# BusDistribution.net
KiCad netlist of a schematic drawn in Altium Designer
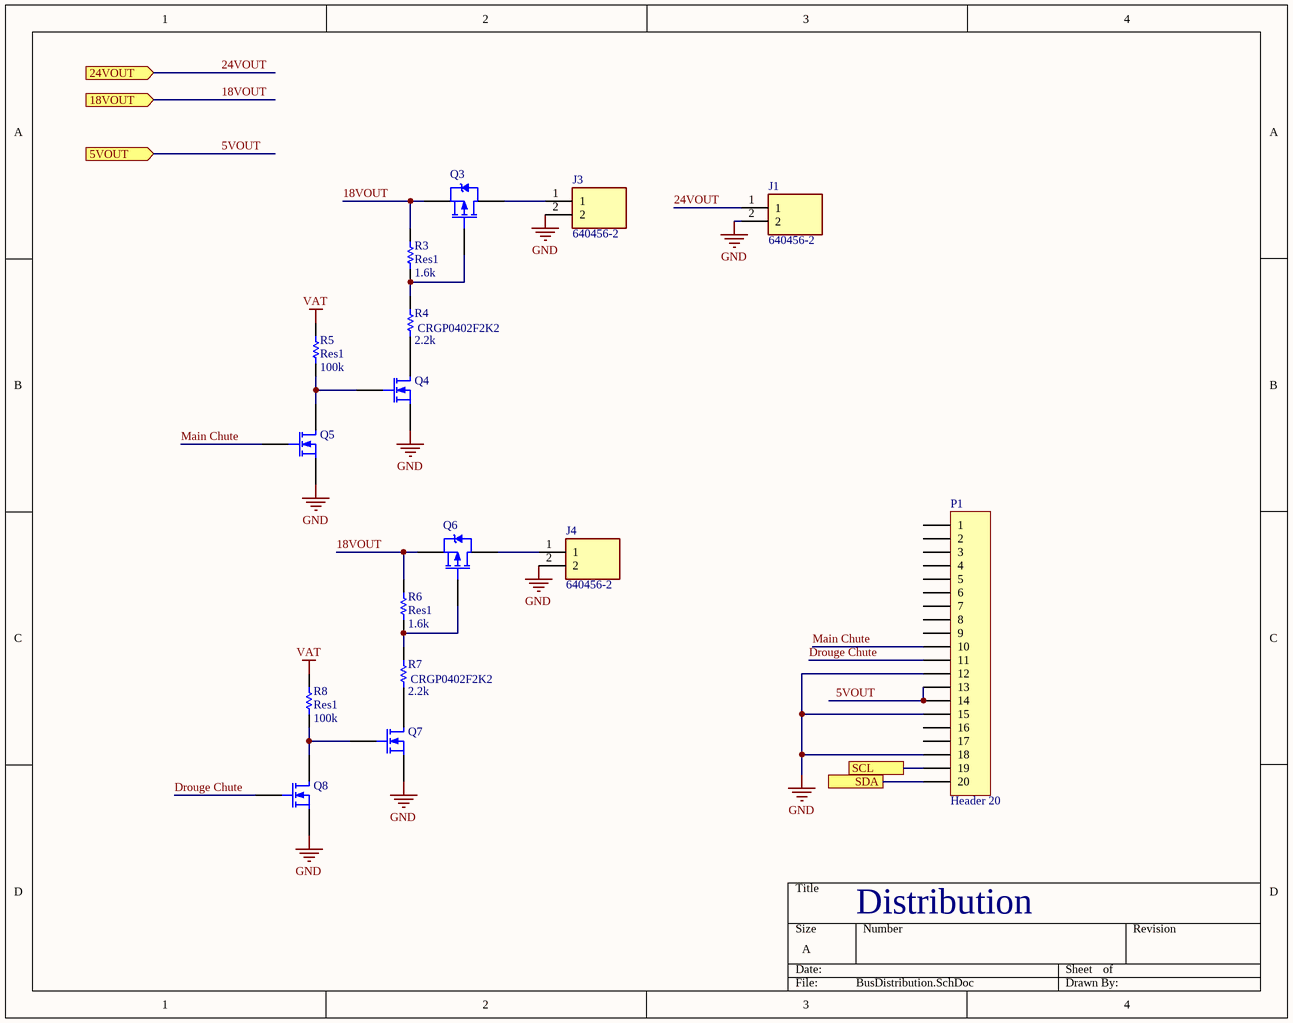
[diagram p0: BusDistribution.SchDoc]

(export (version "E")
  (design (tool "Eeschema 10.0.6"))
  (components
    (comp (ref "J1")
      (value "640456-2")
      (footprint "16404562")
      (description "Connector")
      (fields (field (name "MOUSER PART NUMBER") "571-6404562") (field (name "RS PART NUMBER") "1320355P"))
      (libsource (lib "*") (part "640456-2"))
    )
    (comp (ref "J3")
      (value "640456-2")
      (footprint "16404562")
      (description "Connector")
      (fields (field (name "MOUSER PART NUMBER") "571-6404562") (field (name "RS PART NUMBER") "1320355P"))
      (libsource (lib "*") (part "640456-2"))
    )
    (comp (ref "J4")
      (value "640456-2")
      (footprint "16404562")
      (description "Connector")
      (fields (field (name "MOUSER PART NUMBER") "571-6404562") (field (name "RS PART NUMBER") "1320355P"))
      (libsource (lib "*") (part "640456-2"))
    )
    (comp (ref "P1")
      (value "Header 20")
      (footprint "HDR1X20")
      (description "Header, 20-Pin")
      (fields (field (name "PUBLISHER") "Altium Limited"))
      (libsource (lib "Miscellaneous Connectors") (part "Header 20"))
    )
    (comp (ref "Q3")
      (value "MED power PMOS")
      (footprint "SOT23_L")
      (description "P-Channel Power MOSFET")
      (fields (field (name "PUBLISHER") "Altium Limited"))
      (libsource (lib "Miscellaneous Devices") (part "PMOS-2"))
    )
    (comp (ref "Q4")
      (value "Low Power NMOS")
      (footprint "SOT23_L")
      (description "N-Channel MOSFET")
      (fields (field (name "PUBLISHER") "Altium Limited"))
      (libsource (lib "Miscellaneous Devices") (part "MOSFET-N"))
    )
    (comp (ref "Q5")
      (value "Low power NMOS")
      (footprint "SOT23_L")
      (description "N-Channel MOSFET")
      (fields (field (name "PUBLISHER") "Altium Limited"))
      (libsource (lib "Miscellaneous Devices") (part "MOSFET-N"))
    )
    (comp (ref "Q6")
      (value "MED power PMOS")
      (footprint "SOT23_L")
      (description "P-Channel Power MOSFET")
      (fields (field (name "PUBLISHER") "Altium Limited"))
      (libsource (lib "Miscellaneous Devices") (part "PMOS-2"))
    )
    (comp (ref "Q7")
      (value "Low Power NMOS")
      (footprint "SOT23_L")
      (description "N-Channel MOSFET")
      (fields (field (name "PUBLISHER") "Altium Limited"))
      (libsource (lib "Miscellaneous Devices") (part "MOSFET-N"))
    )
    (comp (ref "Q8")
      (value "Low Power NMOS")
      (footprint "SOT23_L")
      (description "N-Channel MOSFET")
      (fields (field (name "PUBLISHER") "Altium Limited"))
      (libsource (lib "Miscellaneous Devices") (part "MOSFET-N"))
    )
    (comp (ref "R3")
      (value "Res1")
      (footprint "0402")
      (description "Resistor")
      (fields (field (name "ALTIUM_VALUE") "1.6k") (field (name "PUBLISHER") "Altium Limited"))
      (libsource (lib "Miscellaneous Devices") (part "Res1"))
    )
    (comp (ref "R4")
      (value "CRGP0402F2K2")
      (footprint "0402")
      (description "2.2 kOhms ±1% 0.125W, 1/8W Chip Resistor 0402 (1005 Metric) Pulse Withstanding Thick Film")
      (fields (field (name "ALTIUM_VALUE") "2.2k") (field (name "MFG") "TE Connectivity Passive Product"))
      (libsource (lib "Miscellaneous Devices") (part "Res1"))
    )
    (comp (ref "R5")
      (value "Res1")
      (footprint "0402")
      (description "Resistor")
      (fields (field (name "ALTIUM_VALUE") "100k") (field (name "PUBLISHER") "Altium Limited"))
      (libsource (lib "Miscellaneous Devices") (part "Res1"))
    )
    (comp (ref "R6")
      (value "Res1")
      (footprint "0402")
      (description "Resistor")
      (fields (field (name "ALTIUM_VALUE") "1.6k") (field (name "PUBLISHER") "Altium Limited"))
      (libsource (lib "Miscellaneous Devices") (part "Res1"))
    )
    (comp (ref "R7")
      (value "CRGP0402F2K2")
      (footprint "0402")
      (description "2.2 kOhms ±1% 0.125W, 1/8W Chip Resistor 0402 (1005 Metric) Pulse Withstanding Thick Film")
      (fields (field (name "ALTIUM_VALUE") "2.2k") (field (name "MFG") "TE Connectivity Passive Product"))
      (libsource (lib "Miscellaneous Devices") (part "Res1"))
    )
    (comp (ref "R8")
      (value "Res1")
      (footprint "0402")
      (description "Resistor")
      (fields (field (name "ALTIUM_VALUE") "100k") (field (name "PUBLISHER") "Altium Limited"))
      (libsource (lib "Miscellaneous Devices") (part "Res1"))
    )
  )
  (nets
    (net (code "1") (name "/5VOUT") (class "Default")
      (node (ref "P1") (pin "13") (pinfunction "13_13") (pintype "passive"))
      (node (ref "P1") (pin "14") (pinfunction "14_14") (pintype "passive"))
    )
    (net (code "2") (name "/18VOUT") (class "Default")
      (node (ref "Q3") (pin "3") (pinfunction "S_3") (pintype "passive"))
      (node (ref "Q6") (pin "3") (pinfunction "S_3") (pintype "passive"))
      (node (ref "R3") (pin "2") (pinfunction "2_2") (pintype "passive"))
      (node (ref "R6") (pin "2") (pinfunction "2_2") (pintype "passive"))
    )
    (net (code "3") (name "/24VOUT") (class "Default")
      (node (ref "J1") (pin "1") (pinfunction "1_1") (pintype "passive"))
    )
    (net (code "4") (name "/Drouge Chute") (class "Default")
      (node (ref "P1") (pin "11") (pinfunction "11_11") (pintype "passive"))
      (node (ref "Q8") (pin "2") (pinfunction "G_2") (pintype "passive"))
    )
    (net (code "5") (name "/Main Chute") (class "Default")
      (node (ref "P1") (pin "10") (pinfunction "10_10") (pintype "passive"))
      (node (ref "Q5") (pin "2") (pinfunction "G_2") (pintype "passive"))
    )
    (net (code "6") (name "/SCL") (class "Default")
      (node (ref "P1") (pin "19") (pinfunction "19_19") (pintype "passive"))
    )
    (net (code "7") (name "/SDA") (class "Default")
      (node (ref "P1") (pin "20") (pinfunction "20_20") (pintype "passive"))
    )
    (net (code "8") (name "GND") (class "Default")
      (node (ref "J1") (pin "2") (pinfunction "2_2") (pintype "passive"))
      (node (ref "J3") (pin "2") (pinfunction "2_2") (pintype "passive"))
      (node (ref "J4") (pin "2") (pinfunction "2_2") (pintype "passive"))
      (node (ref "P1") (pin "12") (pinfunction "12_12") (pintype "passive"))
      (node (ref "P1") (pin "15") (pinfunction "15_15") (pintype "passive"))
      (node (ref "P1") (pin "18") (pinfunction "18_18") (pintype "passive"))
      (node (ref "Q4") (pin "3") (pinfunction "S_3") (pintype "passive"))
      (node (ref "Q5") (pin "3") (pinfunction "S_3") (pintype "passive"))
      (node (ref "Q7") (pin "3") (pinfunction "S_3") (pintype "passive"))
      (node (ref "Q8") (pin "3") (pinfunction "S_3") (pintype "passive"))
    )
    (net (code "9") (name "Net-(Q3-D)") (class "Default")
      (node (ref "J3") (pin "1") (pinfunction "1_1") (pintype "passive"))
      (node (ref "Q3") (pin "2") (pinfunction "D_2") (pintype "passive"))
    )
    (net (code "10") (name "Net-(Q3-G)") (class "Default")
      (node (ref "Q3") (pin "1") (pinfunction "G_1") (pintype "passive"))
      (node (ref "R3") (pin "1") (pinfunction "1_1") (pintype "passive"))
      (node (ref "R4") (pin "2") (pinfunction "2_2") (pintype "passive"))
    )
    (net (code "11") (name "Net-(Q4-D)") (class "Default")
      (node (ref "Q4") (pin "1") (pinfunction "D_1") (pintype "passive"))
      (node (ref "R4") (pin "1") (pinfunction "1_1") (pintype "passive"))
    )
    (net (code "12") (name "Net-(Q4-G)") (class "Default")
      (node (ref "Q4") (pin "2") (pinfunction "G_2") (pintype "passive"))
      (node (ref "Q5") (pin "1") (pinfunction "D_1") (pintype "passive"))
      (node (ref "R5") (pin "1") (pinfunction "1_1") (pintype "passive"))
    )
    (net (code "13") (name "Net-(Q6-D)") (class "Default")
      (node (ref "J4") (pin "1") (pinfunction "1_1") (pintype "passive"))
      (node (ref "Q6") (pin "2") (pinfunction "D_2") (pintype "passive"))
    )
    (net (code "14") (name "Net-(Q6-G)") (class "Default")
      (node (ref "Q6") (pin "1") (pinfunction "G_1") (pintype "passive"))
      (node (ref "R6") (pin "1") (pinfunction "1_1") (pintype "passive"))
      (node (ref "R7") (pin "2") (pinfunction "2_2") (pintype "passive"))
    )
    (net (code "15") (name "Net-(Q7-D)") (class "Default")
      (node (ref "Q7") (pin "1") (pinfunction "D_1") (pintype "passive"))
      (node (ref "R7") (pin "1") (pinfunction "1_1") (pintype "passive"))
    )
    (net (code "16") (name "Net-(Q7-G)") (class "Default")
      (node (ref "Q7") (pin "2") (pinfunction "G_2") (pintype "passive"))
      (node (ref "Q8") (pin "1") (pinfunction "D_1") (pintype "passive"))
      (node (ref "R8") (pin "1") (pinfunction "1_1") (pintype "passive"))
    )
    (net (code "17") (name "VAT") (class "Default")
      (node (ref "R5") (pin "2") (pinfunction "2_2") (pintype "passive"))
      (node (ref "R8") (pin "2") (pinfunction "2_2") (pintype "passive"))
    )
    (net (code "18") (name "unconnected-(P1-Pad1)") (class "Default")
      (node (ref "P1") (pin "1") (pinfunction "1_1") (pintype "passive"))
    )
    (net (code "19") (name "unconnected-(P1-Pad2)") (class "Default")
      (node (ref "P1") (pin "2") (pinfunction "2_2") (pintype "passive"))
    )
    (net (code "20") (name "unconnected-(P1-Pad3)") (class "Default")
      (node (ref "P1") (pin "3") (pinfunction "3_3") (pintype "passive"))
    )
    (net (code "21") (name "unconnected-(P1-Pad4)") (class "Default")
      (node (ref "P1") (pin "4") (pinfunction "4_4") (pintype "passive"))
    )
    (net (code "22") (name "unconnected-(P1-Pad5)") (class "Default")
      (node (ref "P1") (pin "5") (pinfunction "5_5") (pintype "passive"))
    )
    (net (code "23") (name "unconnected-(P1-Pad6)") (class "Default")
      (node (ref "P1") (pin "6") (pinfunction "6_6") (pintype "passive"))
    )
    (net (code "24") (name "unconnected-(P1-Pad7)") (class "Default")
      (node (ref "P1") (pin "7") (pinfunction "7_7") (pintype "passive"))
    )
    (net (code "25") (name "unconnected-(P1-Pad8)") (class "Default")
      (node (ref "P1") (pin "8") (pinfunction "8_8") (pintype "passive"))
    )
    (net (code "26") (name "unconnected-(P1-Pad9)") (class "Default")
      (node (ref "P1") (pin "9") (pinfunction "9_9") (pintype "passive"))
    )
    (net (code "27") (name "unconnected-(P1-Pad16)") (class "Default")
      (node (ref "P1") (pin "16") (pinfunction "16_16") (pintype "passive"))
    )
    (net (code "28") (name "unconnected-(P1-Pad17)") (class "Default")
      (node (ref "P1") (pin "17") (pinfunction "17_17") (pintype "passive"))
    )
  )
)
